# bbb_xbee.net
KiCad netlist of a schematic drawn in EAGLE
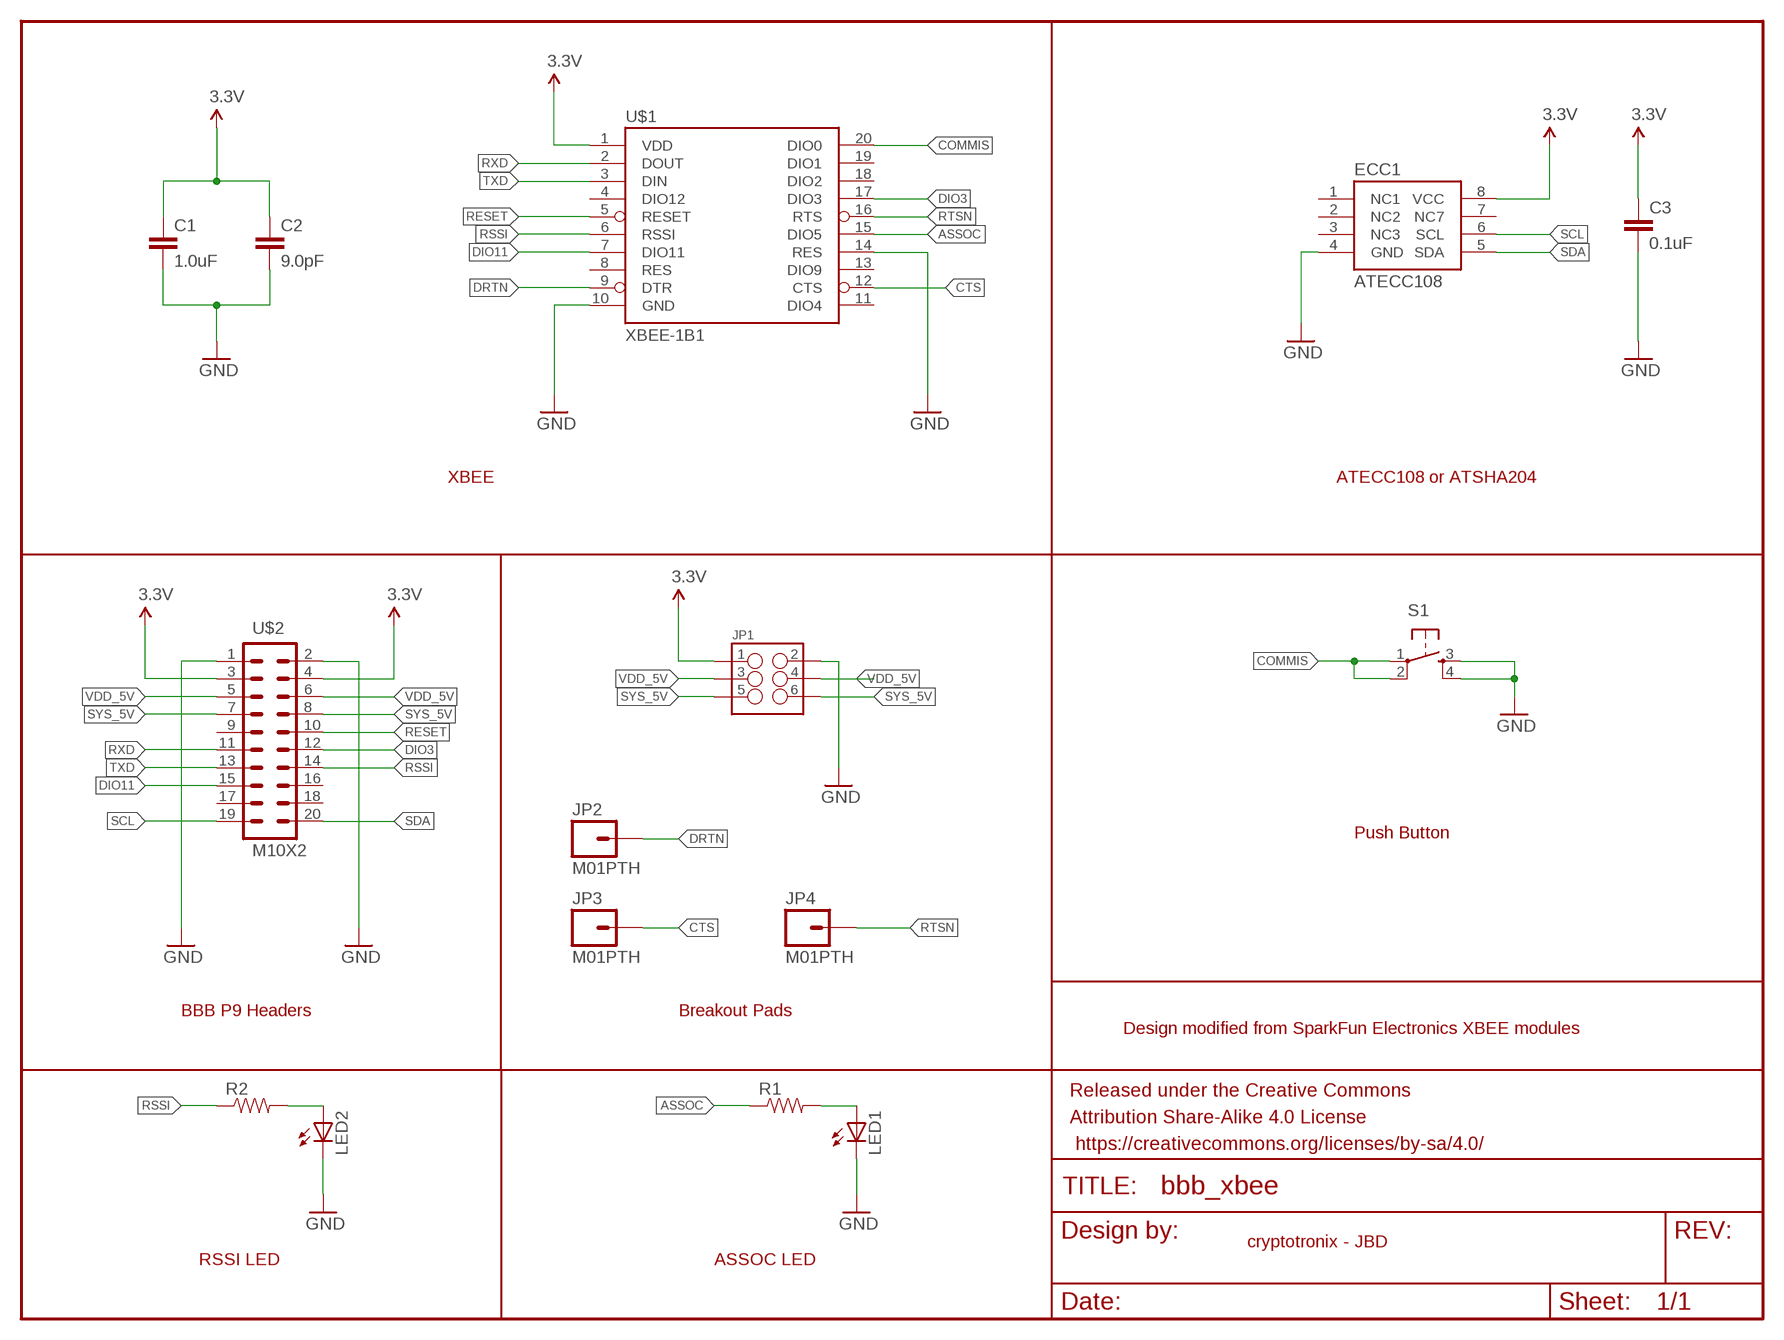
[diagram p0: schematic, sheet 1]

(export (version "E")
  (design (tool "Eeschema 10.0.6"))
  (components
    (comp (ref "C1")
      (value "1.0uF")
      (footprint "eagle-import:0603-CAP")
      (libsource (lib "eagle-import") (part "1.0UF-16V-10%(0603)"))
    )
    (comp (ref "C2")
      (value "9.0pF")
      (footprint "eagle-import:0603-CAP")
      (libsource (lib "eagle-import") (part "9.0PF-50V-10%(0603)"))
    )
    (comp (ref "C3")
      (value "0.1uF")
      (footprint "eagle-import:0603-CAP")
      (libsource (lib "eagle-import") (part "0.1UF-100V-10%(0603)"))
    )
    (comp (ref "ECC1")
      (value "ATECC108")
      (footprint "eagle-import:SOIC8")
      (libsource (lib "eagle-import") (part "ATECC108"))
    )
    (comp (ref "FRAME1")
      (value "FRAME-LETTER")
      (footprint "eagle-import:CREATIVE_COMMONS")
      (libsource (lib "eagle-import") (part "FRAME-LETTER"))
    )
    (comp (ref "JP1")
      (value "M03X22X3_SILK_SM")
      (footprint "eagle-import:2X3")
      (libsource (lib "eagle-import") (part "M03X22X3_SILK_SM"))
    )
    (comp (ref "JP2")
      (value "M01PTH")
      (footprint "eagle-import:1X01")
      (libsource (lib "eagle-import") (part "M01PTH"))
    )
    (comp (ref "JP3")
      (value "M01PTH")
      (footprint "eagle-import:1X01")
      (libsource (lib "eagle-import") (part "M01PTH"))
    )
    (comp (ref "JP4")
      (value "M01PTH")
      (footprint "eagle-import:1X01")
      (libsource (lib "eagle-import") (part "M01PTH"))
    )
    (comp (ref "LED1")
      (value "LED-RED0603")
      (footprint "eagle-import:LED-0603")
      (libsource (lib "eagle-import") (part "LED-RED0603"))
    )
    (comp (ref "LED2")
      (value "LED-BLUE0603")
      (footprint "eagle-import:LED-0603")
      (libsource (lib "eagle-import") (part "LED-BLUE0603"))
    )
    (comp (ref "R1")
      (value "RESISTOR0603")
      (footprint "eagle-import:0603-RES")
      (libsource (lib "eagle-import") (part "RESISTOR0603"))
    )
    (comp (ref "R2")
      (value "RESISTOR0603")
      (footprint "eagle-import:0603-RES")
      (libsource (lib "eagle-import") (part "RESISTOR0603"))
    )
    (comp (ref "S1")
      (value "TAC_SWITCHPTH")
      (footprint "eagle-import:TACTILE-PTH")
      (libsource (lib "eagle-import") (part "TAC_SWITCHPTH"))
    )
    (comp (ref "U$1")
      (value "XBEE-1B1")
      (footprint "eagle-import:XBEE-1")
      (libsource (lib "eagle-import") (part "XBEE-1B1"))
    )
    (comp (ref "U$2")
      (value "M10X2")
      (footprint "eagle-import:2X10")
      (libsource (lib "eagle-import") (part "M10X2"))
    )
  )
  (nets
    (net (code "1") (name "3.3V") (class "Default")
      (node (ref "C1") (pin "1") (pinfunction "1_1") (pintype "passive"))
      (node (ref "C2") (pin "1") (pinfunction "1_1") (pintype "passive"))
      (node (ref "C3") (pin "1") (pinfunction "1_1") (pintype "passive"))
      (node (ref "ECC1") (pin "8") (pinfunction "VCC_8") (pintype "power_in"))
      (node (ref "JP1") (pin "1") (pinfunction "1_1") (pintype "bidirectional"))
      (node (ref "U$1") (pin "1") (pinfunction "VDD_1") (pintype "power_in"))
      (node (ref "U$2") (pin "3") (pinfunction "3_3") (pintype "passive"))
      (node (ref "U$2") (pin "4") (pinfunction "4_4") (pintype "passive"))
    )
    (net (code "2") (name "ASSOC") (class "Default")
      (node (ref "R1") (pin "1") (pinfunction "1_1") (pintype "passive"))
      (node (ref "U$1") (pin "15") (pinfunction "DIO5_15") (pintype "bidirectional"))
    )
    (net (code "3") (name "COMMIS") (class "Default")
      (node (ref "S1") (pin "1") (pinfunction "1_1") (pintype "passive"))
      (node (ref "S1") (pin "2") (pinfunction "2_2") (pintype "passive"))
      (node (ref "U$1") (pin "20") (pinfunction "DIO0_20") (pintype "bidirectional"))
    )
    (net (code "4") (name "CTS") (class "Default")
      (node (ref "JP3") (pin "1") (pinfunction "1_1") (pintype "passive"))
      (node (ref "U$1") (pin "12") (pinfunction "CTS_12") (pintype "output"))
    )
    (net (code "5") (name "DIO3") (class "Default")
      (node (ref "U$1") (pin "17") (pinfunction "DIO3_17") (pintype "bidirectional"))
      (node (ref "U$2") (pin "12") (pinfunction "12_12") (pintype "passive"))
    )
    (net (code "6") (name "DIO11") (class "Default")
      (node (ref "U$1") (pin "7") (pinfunction "DIO11_7") (pintype "bidirectional"))
      (node (ref "U$2") (pin "15") (pinfunction "15_15") (pintype "passive"))
    )
    (net (code "7") (name "DRTN") (class "Default")
      (node (ref "JP2") (pin "1") (pinfunction "1_1") (pintype "passive"))
      (node (ref "U$1") (pin "9") (pinfunction "DTR_9") (pintype "bidirectional"))
    )
    (net (code "8") (name "GND") (class "Default")
      (node (ref "C1") (pin "2") (pinfunction "2_2") (pintype "passive"))
      (node (ref "C2") (pin "2") (pinfunction "2_2") (pintype "passive"))
      (node (ref "C3") (pin "2") (pinfunction "2_2") (pintype "passive"))
      (node (ref "ECC1") (pin "4") (pinfunction "GND_4") (pintype "power_in"))
      (node (ref "JP1") (pin "2") (pinfunction "2_2") (pintype "bidirectional"))
      (node (ref "LED1") (pin "C") (pinfunction "C_C") (pintype "passive"))
      (node (ref "LED2") (pin "C") (pinfunction "C_C") (pintype "passive"))
      (node (ref "S1") (pin "3") (pinfunction "3_3") (pintype "passive"))
      (node (ref "S1") (pin "4") (pinfunction "4_4") (pintype "passive"))
      (node (ref "U$1") (pin "10") (pinfunction "GND_10") (pintype "power_in"))
      (node (ref "U$1") (pin "14") (pinfunction "RES_14") (pintype "bidirectional"))
      (node (ref "U$2") (pin "1") (pinfunction "1_1") (pintype "passive"))
      (node (ref "U$2") (pin "2") (pinfunction "2_2") (pintype "passive"))
    )
    (net (code "9") (name "Net-(LED1-PadA)") (class "Default")
      (node (ref "LED1") (pin "A") (pinfunction "A_A") (pintype "passive"))
      (node (ref "R1") (pin "2") (pinfunction "2_2") (pintype "passive"))
    )
    (net (code "10") (name "Net-(LED2-PadA)") (class "Default")
      (node (ref "LED2") (pin "A") (pinfunction "A_A") (pintype "passive"))
      (node (ref "R2") (pin "2") (pinfunction "2_2") (pintype "passive"))
    )
    (net (code "11") (name "RESET") (class "Default")
      (node (ref "U$1") (pin "5") (pinfunction "RESET_5") (pintype "input"))
      (node (ref "U$2") (pin "10") (pinfunction "10_10") (pintype "passive"))
    )
    (net (code "12") (name "RSSI") (class "Default")
      (node (ref "R2") (pin "1") (pinfunction "1_1") (pintype "passive"))
      (node (ref "U$1") (pin "6") (pinfunction "RSSI_6") (pintype "bidirectional"))
      (node (ref "U$2") (pin "14") (pinfunction "14_14") (pintype "passive"))
    )
    (net (code "13") (name "RTSN") (class "Default")
      (node (ref "JP4") (pin "1") (pinfunction "1_1") (pintype "passive"))
      (node (ref "U$1") (pin "16") (pinfunction "RTS_16") (pintype "input"))
    )
    (net (code "14") (name "RXD") (class "Default")
      (node (ref "U$1") (pin "2") (pinfunction "DOUT_2") (pintype "output"))
      (node (ref "U$2") (pin "11") (pinfunction "11_11") (pintype "passive"))
    )
    (net (code "15") (name "SCL") (class "Default")
      (node (ref "ECC1") (pin "6") (pinfunction "SCL_6") (pintype "bidirectional"))
      (node (ref "U$2") (pin "19") (pinfunction "19_19") (pintype "passive"))
    )
    (net (code "16") (name "SDA") (class "Default")
      (node (ref "ECC1") (pin "5") (pinfunction "SDA_5") (pintype "bidirectional"))
      (node (ref "U$2") (pin "20") (pinfunction "20_20") (pintype "passive"))
    )
    (net (code "17") (name "SYS_5V") (class "Default")
      (node (ref "JP1") (pin "5") (pinfunction "5_5") (pintype "bidirectional"))
      (node (ref "JP1") (pin "6") (pinfunction "6_6") (pintype "bidirectional"))
      (node (ref "U$2") (pin "7") (pinfunction "7_7") (pintype "passive"))
      (node (ref "U$2") (pin "8") (pinfunction "8_8") (pintype "passive"))
    )
    (net (code "18") (name "TXD") (class "Default")
      (node (ref "U$1") (pin "3") (pinfunction "DIN_3") (pintype "input"))
      (node (ref "U$2") (pin "13") (pinfunction "13_13") (pintype "passive"))
    )
    (net (code "19") (name "VDD_5V") (class "Default")
      (node (ref "JP1") (pin "3") (pinfunction "3_3") (pintype "bidirectional"))
      (node (ref "JP1") (pin "4") (pinfunction "4_4") (pintype "bidirectional"))
      (node (ref "U$2") (pin "5") (pinfunction "5_5") (pintype "passive"))
      (node (ref "U$2") (pin "6") (pinfunction "6_6") (pintype "passive"))
    )
    (net (code "20") (name "unconnected-(ECC1-NC1-Pad1)") (class "Default")
      (node (ref "ECC1") (pin "1") (pinfunction "NC1_1") (pintype "bidirectional"))
    )
    (net (code "21") (name "unconnected-(ECC1-NC2-Pad2)") (class "Default")
      (node (ref "ECC1") (pin "2") (pinfunction "NC2_2") (pintype "no_connect"))
    )
    (net (code "22") (name "unconnected-(ECC1-NC3-Pad3)") (class "Default")
      (node (ref "ECC1") (pin "3") (pinfunction "NC3_3") (pintype "no_connect"))
    )
    (net (code "23") (name "unconnected-(ECC1-NC7-Pad7)") (class "Default")
      (node (ref "ECC1") (pin "7") (pinfunction "NC7_7") (pintype "no_connect"))
    )
    (net (code "24") (name "unconnected-(U$1-DIO1-Pad19)") (class "Default")
      (node (ref "U$1") (pin "19") (pinfunction "DIO1_19") (pintype "bidirectional"))
    )
    (net (code "25") (name "unconnected-(U$1-DIO2-Pad18)") (class "Default")
      (node (ref "U$1") (pin "18") (pinfunction "DIO2_18") (pintype "bidirectional"))
    )
    (net (code "26") (name "unconnected-(U$1-DIO4-Pad11)") (class "Default")
      (node (ref "U$1") (pin "11") (pinfunction "DIO4_11") (pintype "bidirectional"))
    )
    (net (code "27") (name "unconnected-(U$1-DIO9-Pad13)") (class "Default")
      (node (ref "U$1") (pin "13") (pinfunction "DIO9_13") (pintype "bidirectional"))
    )
    (net (code "28") (name "unconnected-(U$1-DIO12-Pad4)") (class "Default")
      (node (ref "U$1") (pin "4") (pinfunction "DIO12_4") (pintype "bidirectional"))
    )
    (net (code "29") (name "unconnected-(U$1-RES-Pad8)") (class "Default")
      (node (ref "U$1") (pin "8") (pinfunction "RES_8") (pintype "bidirectional"))
    )
    (net (code "30") (name "unconnected-(U$2-Pad9)") (class "Default")
      (node (ref "U$2") (pin "9") (pinfunction "9_9") (pintype "passive"))
    )
    (net (code "31") (name "unconnected-(U$2-Pad16)") (class "Default")
      (node (ref "U$2") (pin "16") (pinfunction "16_16") (pintype "passive"))
    )
    (net (code "32") (name "unconnected-(U$2-Pad17)") (class "Default")
      (node (ref "U$2") (pin "17") (pinfunction "17_17") (pintype "passive"))
    )
    (net (code "33") (name "unconnected-(U$2-Pad18)") (class "Default")
      (node (ref "U$2") (pin "18") (pinfunction "18_18") (pintype "passive"))
    )
  )
)
